# LICL_Comparator.net
KiCad netlist of a schematic drawn in EAGLE
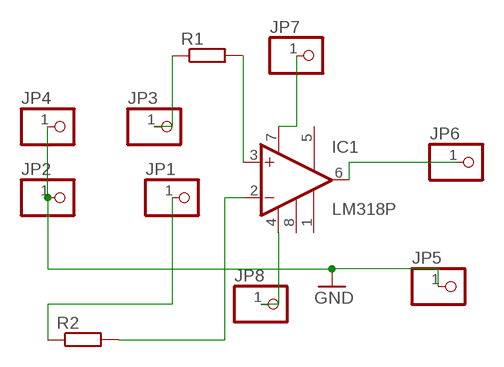
[diagram p0: schematic, sheet 1]

(export (version "E")
  (design (tool "Eeschema 10.0.6"))
  (components
    (comp (ref "IC1")
      (value "LM318P")
      (footprint "eagle-import:DIL08")
      (libsource (lib "eagle-import") (part "LM18P3"))
    )
    (comp (ref "JP1")
      (value "PINHD-1X1")
      (footprint "eagle-import:1X01")
      (libsource (lib "eagle-import") (part "PINHD-1X1"))
    )
    (comp (ref "JP2")
      (value "PINHD-1X1")
      (footprint "eagle-import:1X01")
      (libsource (lib "eagle-import") (part "PINHD-1X1"))
    )
    (comp (ref "JP3")
      (value "PINHD-1X1")
      (footprint "eagle-import:1X01")
      (libsource (lib "eagle-import") (part "PINHD-1X1"))
    )
    (comp (ref "JP4")
      (value "PINHD-1X1")
      (footprint "eagle-import:1X01")
      (libsource (lib "eagle-import") (part "PINHD-1X1"))
    )
    (comp (ref "JP5")
      (value "PINHD-1X1")
      (footprint "eagle-import:1X01")
      (libsource (lib "eagle-import") (part "PINHD-1X1"))
    )
    (comp (ref "JP6")
      (value "PINHD-1X1")
      (footprint "eagle-import:1X01")
      (libsource (lib "eagle-import") (part "PINHD-1X1"))
    )
    (comp (ref "JP7")
      (value "PINHD-1X1")
      (footprint "eagle-import:1X01")
      (libsource (lib "eagle-import") (part "PINHD-1X1"))
    )
    (comp (ref "JP8")
      (value "PINHD-1X1")
      (footprint "eagle-import:1X01")
      (libsource (lib "eagle-import") (part "PINHD-1X1"))
    )
    (comp (ref "R1")
      (value "R-EU_0207/10")
      (footprint "eagle-import:0207_10")
      (libsource (lib "eagle-import") (part "R-EU_0207/10"))
    )
    (comp (ref "R2")
      (value "R-EU_0207/10")
      (footprint "eagle-import:0207_10")
      (libsource (lib "eagle-import") (part "R-EU_0207/10"))
    )
  )
  (nets
    (net (code "1") (name "GND") (class "Default")
      (node (ref "JP2") (pin "1") (pinfunction "1_1") (pintype "passive"))
      (node (ref "JP4") (pin "1") (pinfunction "1_1") (pintype "passive"))
      (node (ref "JP5") (pin "1") (pinfunction "1_1") (pintype "passive"))
    )
    (net (code "2") (name "Net-(IC1-+IN)") (class "Default")
      (node (ref "IC1") (pin "3") (pinfunction "+IN_3") (pintype "input"))
      (node (ref "R1") (pin "2") (pinfunction "2_2") (pintype "passive"))
    )
    (net (code "3") (name "Net-(IC1--IN)") (class "Default")
      (node (ref "IC1") (pin "2") (pinfunction "-IN_2") (pintype "input"))
      (node (ref "R2") (pin "2") (pinfunction "2_2") (pintype "passive"))
    )
    (net (code "4") (name "Net-(IC1-OUT)") (class "Default")
      (node (ref "IC1") (pin "6") (pinfunction "OUT_6") (pintype "output"))
      (node (ref "JP6") (pin "1") (pinfunction "1_1") (pintype "passive"))
    )
    (net (code "5") (name "Net-(IC1-V+)") (class "Default")
      (node (ref "IC1") (pin "7") (pinfunction "V+_7") (pintype "power_in"))
      (node (ref "JP7") (pin "1") (pinfunction "1_1") (pintype "passive"))
    )
    (net (code "6") (name "Net-(IC1-V-)") (class "Default")
      (node (ref "IC1") (pin "4") (pinfunction "V-_4") (pintype "power_in"))
      (node (ref "JP8") (pin "1") (pinfunction "1_1") (pintype "passive"))
    )
    (net (code "7") (name "Net-(JP1-Pad1)") (class "Default")
      (node (ref "JP1") (pin "1") (pinfunction "1_1") (pintype "passive"))
      (node (ref "R2") (pin "1") (pinfunction "1_1") (pintype "passive"))
    )
    (net (code "8") (name "Net-(JP3-Pad1)") (class "Default")
      (node (ref "JP3") (pin "1") (pinfunction "1_1") (pintype "passive"))
      (node (ref "R1") (pin "1") (pinfunction "1_1") (pintype "passive"))
    )
    (net (code "9") (name "unconnected-(IC1-BAL1-Pad1)") (class "Default")
      (node (ref "IC1") (pin "1") (pinfunction "BAL1_1") (pintype "passive"))
    )
    (net (code "10") (name "unconnected-(IC1-BAL2-Pad5)") (class "Default")
      (node (ref "IC1") (pin "5") (pinfunction "BAL2_5") (pintype "passive"))
    )
    (net (code "11") (name "unconnected-(IC1-COMP-Pad8)") (class "Default")
      (node (ref "IC1") (pin "8") (pinfunction "COMP_8") (pintype "passive"))
    )
  )
)
